# CANBedDualGd.net
KiCad netlist of a schematic drawn in EAGLE
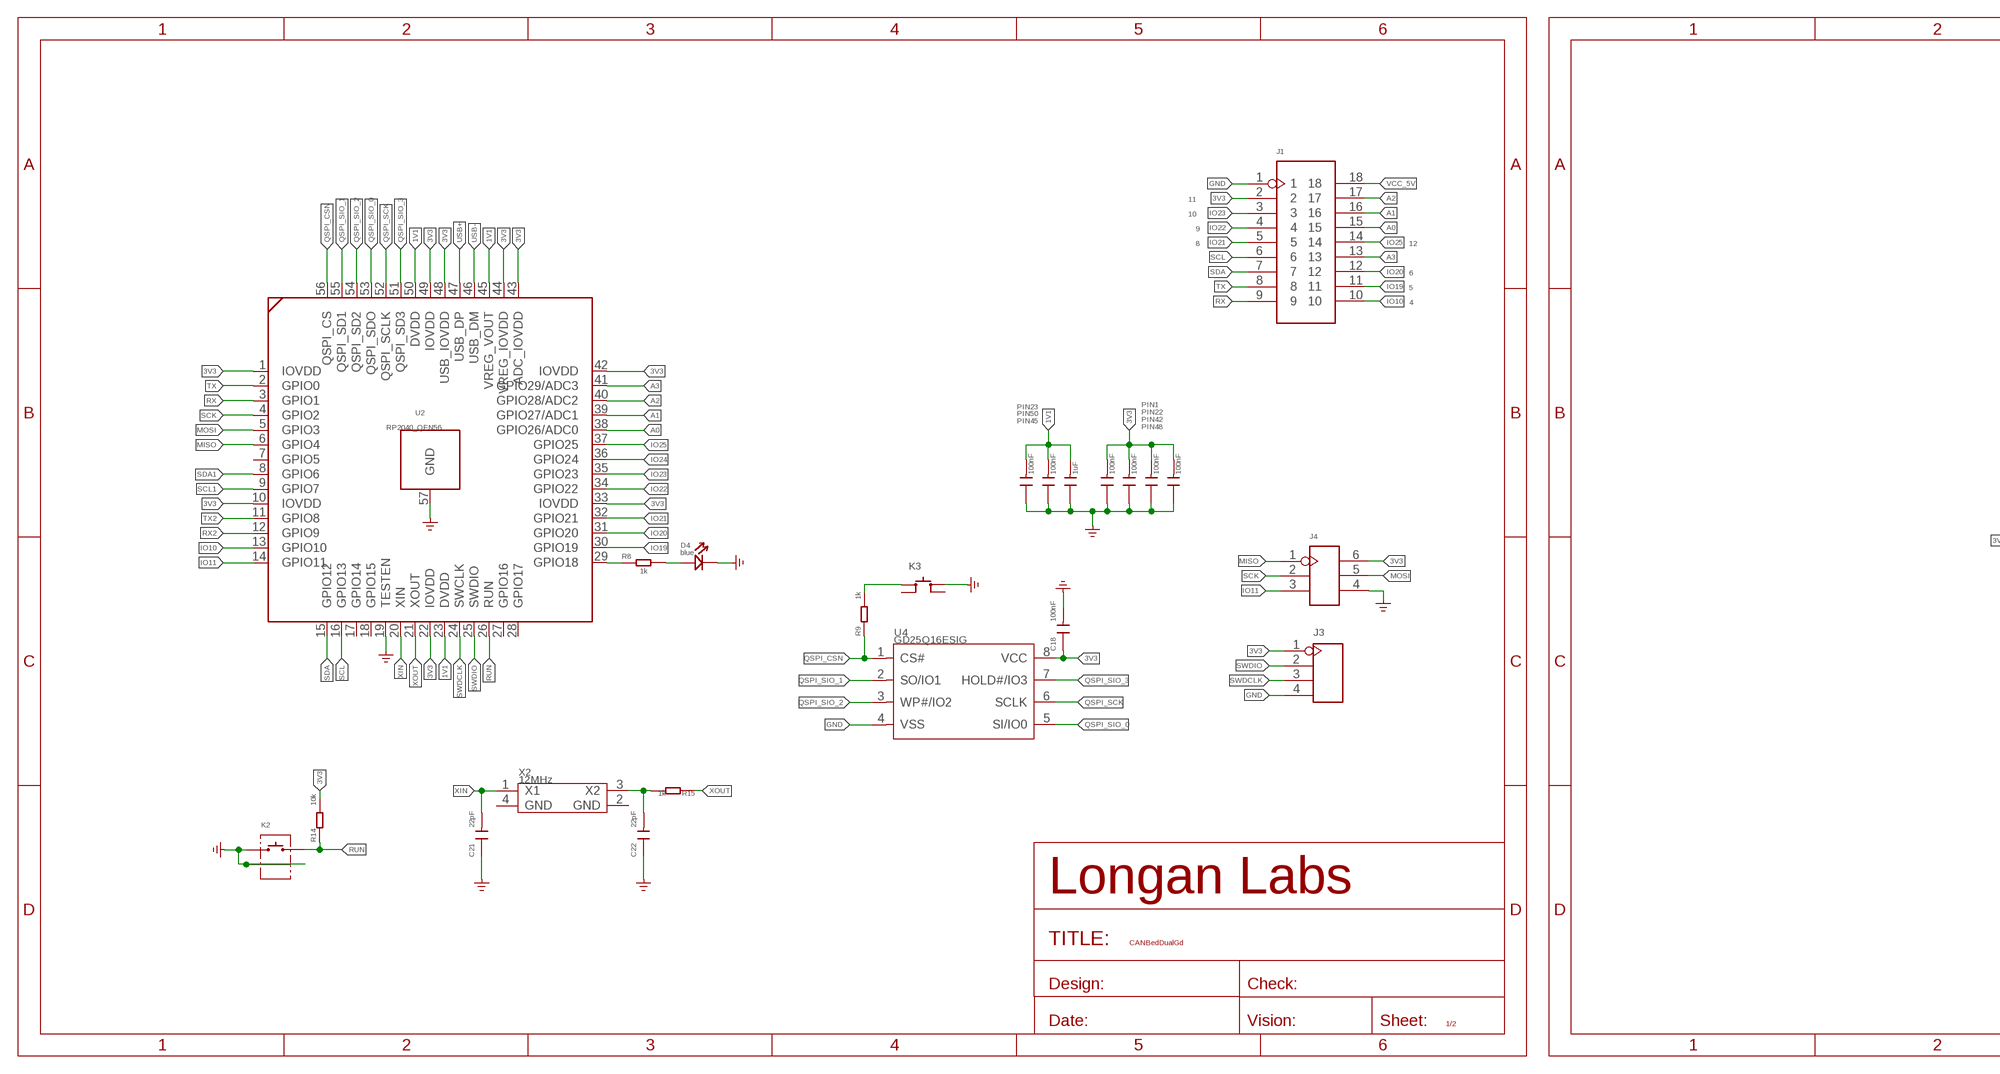
[diagram p0: schematic, sheet 1, part 1 of 2]
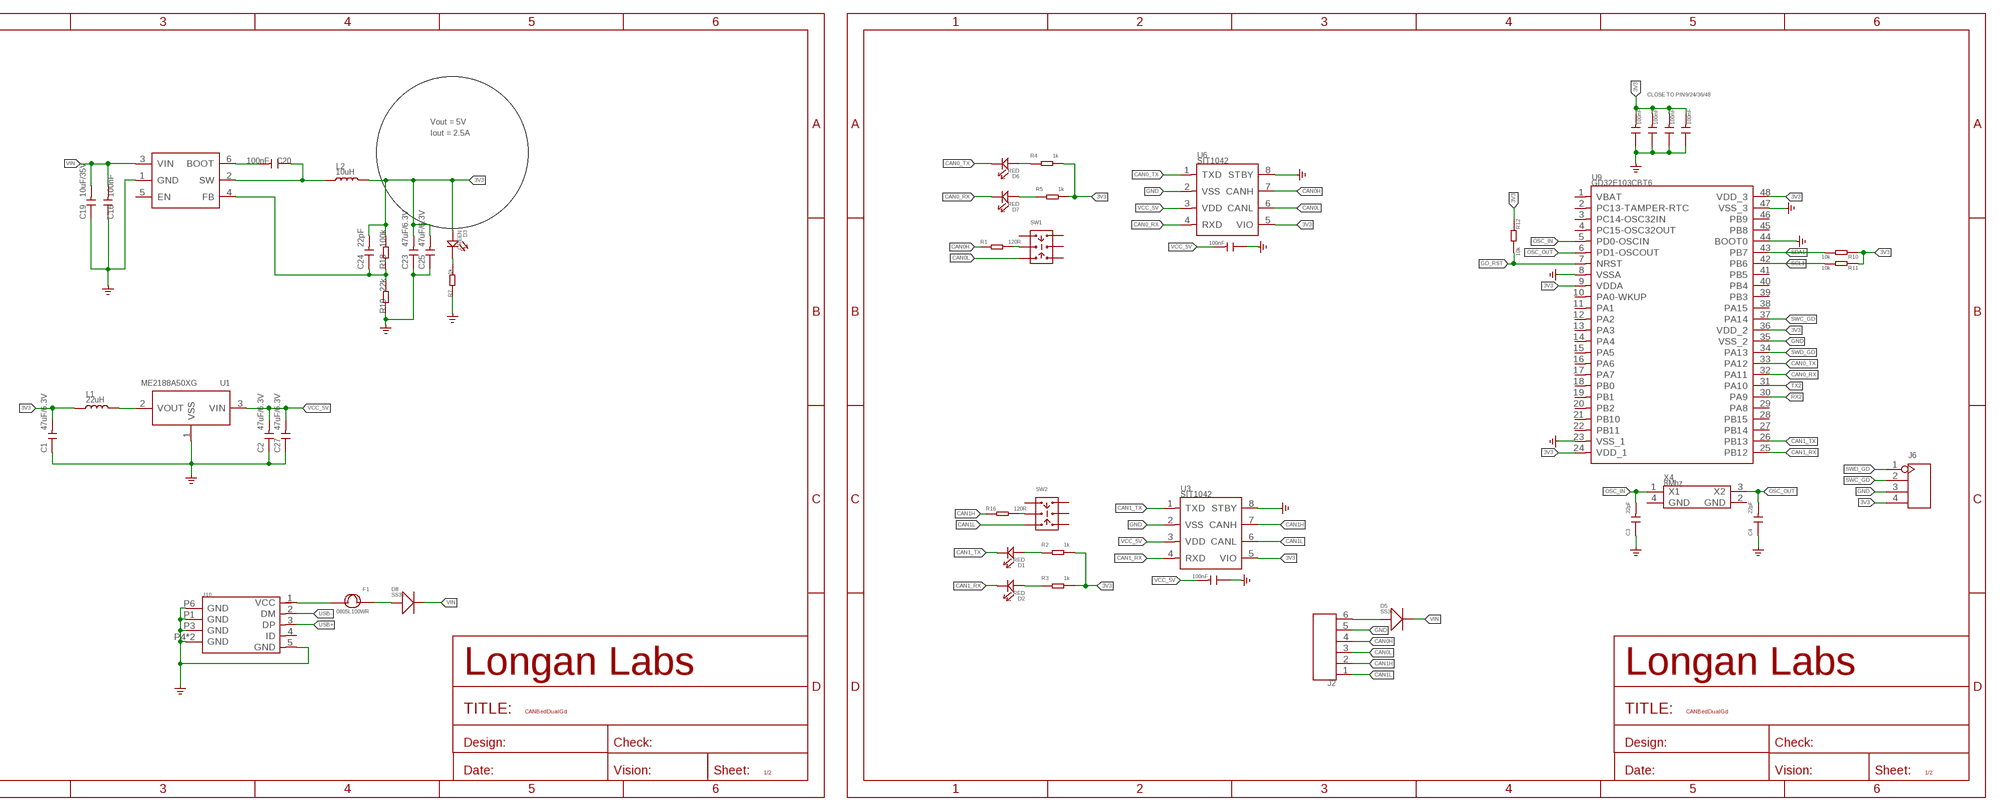
[diagram p1: schematic, sheet 1, part 2 of 2]

(export (version "E")
  (design (tool "Eeschema 10.0.6"))
  (components
    (comp (ref "C1")
      (value "47uF/6.3V")
      (footprint "eagle-import:C0805")
      (libsource (lib "eagle-import") (part "CAP-0805"))
    )
    (comp (ref "C2")
      (value "47uF/6.3V")
      (footprint "eagle-import:C0805")
      (libsource (lib "eagle-import") (part "CAP-0805"))
    )
    (comp (ref "C3")
      (value "22pF")
      (footprint "eagle-import:C0603")
      (libsource (lib "eagle-import") (part "CAP-0603"))
    )
    (comp (ref "C4")
      (value "22pF")
      (footprint "eagle-import:C0603")
      (libsource (lib "eagle-import") (part "CAP-0603"))
    )
    (comp (ref "C5")
      (value "100nF")
      (footprint "eagle-import:C0603")
      (libsource (lib "eagle-import") (part "CAP-0603"))
    )
    (comp (ref "C6")
      (value "100nF")
      (footprint "eagle-import:C0603")
      (libsource (lib "eagle-import") (part "CAP-0603"))
    )
    (comp (ref "C7")
      (value "100nF")
      (footprint "eagle-import:C0603")
      (libsource (lib "eagle-import") (part "CAP-0603"))
    )
    (comp (ref "C8")
      (value "100nF")
      (footprint "eagle-import:C0603")
      (libsource (lib "eagle-import") (part "CAP-0603"))
    )
    (comp (ref "C9")
      (value "100nF")
      (footprint "eagle-import:C0603")
      (libsource (lib "eagle-import") (part "CAP-0603"))
    )
    (comp (ref "C10")
      (value "100nF")
      (footprint "eagle-import:C0603")
      (libsource (lib "eagle-import") (part "CAP-0603"))
    )
    (comp (ref "C11")
      (value "1uF")
      (footprint "eagle-import:C0603")
      (libsource (lib "eagle-import") (part "CAP-0603"))
    )
    (comp (ref "C12")
      (value "100nF")
      (footprint "eagle-import:C0603")
      (libsource (lib "eagle-import") (part "CAP-0603"))
    )
    (comp (ref "C13")
      (value "100nF")
      (footprint "eagle-import:C0603")
      (libsource (lib "eagle-import") (part "CAP-0603"))
    )
    (comp (ref "C14")
      (value "100nF")
      (footprint "eagle-import:C0603")
      (libsource (lib "eagle-import") (part "CAP-0603"))
    )
    (comp (ref "C15")
      (value "100nF")
      (footprint "eagle-import:C0603")
      (libsource (lib "eagle-import") (part "CAP-0603"))
    )
    (comp (ref "C16")
      (value "100nF")
      (footprint "eagle-import:C0603")
      (libsource (lib "eagle-import") (part "CAP-0603"))
    )
    (comp (ref "C17")
      (value "100nF")
      (footprint "eagle-import:C0603")
      (libsource (lib "eagle-import") (part "CAP-0603"))
    )
    (comp (ref "C18")
      (value "100nF")
      (footprint "eagle-import:C0603")
      (libsource (lib "eagle-import") (part "CAP-0603"))
    )
    (comp (ref "C19")
      (value "10uF/35V")
      (footprint "eagle-import:C1206")
      (libsource (lib "eagle-import") (part "CAP-1206"))
    )
    (comp (ref "C20")
      (value "100nF")
      (footprint "eagle-import:C0603")
      (libsource (lib "eagle-import") (part "CAP-0603"))
    )
    (comp (ref "C21")
      (value "22pF")
      (footprint "eagle-import:C0603")
      (libsource (lib "eagle-import") (part "CAP-0603"))
    )
    (comp (ref "C22")
      (value "22pF")
      (footprint "eagle-import:C0603")
      (libsource (lib "eagle-import") (part "CAP-0603"))
    )
    (comp (ref "C23")
      (value "47uF/6.3V")
      (footprint "eagle-import:C0805")
      (libsource (lib "eagle-import") (part "CAP-0805"))
    )
    (comp (ref "C24")
      (value "22pF")
      (footprint "eagle-import:C0603")
      (libsource (lib "eagle-import") (part "CAP-0603"))
    )
    (comp (ref "C25")
      (value "47uF/6.3V")
      (footprint "eagle-import:C0805")
      (libsource (lib "eagle-import") (part "CAP-0805"))
    )
    (comp (ref "C26")
      (value "100nF")
      (footprint "eagle-import:C0603")
      (libsource (lib "eagle-import") (part "CAP-0603"))
    )
    (comp (ref "C27")
      (value "47uF/6.3V")
      (footprint "eagle-import:C0805")
      (libsource (lib "eagle-import") (part "CAP-0805"))
    )
    (comp (ref "D1")
      (value "RED")
      (footprint "eagle-import:LED-0603")
      (libsource (lib "eagle-import") (part "LED'0603'"))
    )
    (comp (ref "D2")
      (value "RED")
      (footprint "eagle-import:LED-0603")
      (libsource (lib "eagle-import") (part "LED'0603'"))
    )
    (comp (ref "D3")
      (value "GREEN")
      (footprint "eagle-import:LED-0603")
      (libsource (lib "eagle-import") (part "LED'0603'"))
    )
    (comp (ref "D4")
      (value "blue")
      (footprint "eagle-import:LED-0603")
      (libsource (lib "eagle-import") (part "LED'0603'"))
    )
    (comp (ref "D5")
      (value "SS32")
      (footprint "eagle-import:DO-214AC")
      (libsource (lib "eagle-import") (part "DIODE'SMA'"))
    )
    (comp (ref "D6")
      (value "RED")
      (footprint "eagle-import:LED-0603")
      (libsource (lib "eagle-import") (part "LED'0603'"))
    )
    (comp (ref "D7")
      (value "RED")
      (footprint "eagle-import:LED-0603")
      (libsource (lib "eagle-import") (part "LED'0603'"))
    )
    (comp (ref "D8")
      (value "SS32")
      (footprint "eagle-import:DO-214AC")
      (libsource (lib "eagle-import") (part "DIODE'SMA'"))
    )
    (comp (ref "F1")
      (value "0805L100WR")
      (footprint "eagle-import:F0805")
      (libsource (lib "eagle-import") (part "FUSE0805"))
    )
    (comp (ref "J1")
      (value "HEADER-2X9P-2.54")
      (footprint "eagle-import:H2X9-2.54")
      (libsource (lib "eagle-import") (part "HEADER-2X9P-2.54"))
    )
    (comp (ref "J2")
      (value "SCREW-TERMINAL-6P-3.5")
      (footprint "eagle-import:H6-3.5-21.7X7.0MM")
      (libsource (lib "eagle-import") (part "SCREW-TERMINAL-6P-3.5"))
    )
    (comp (ref "J3")
      (value "HEADER-4P-SMD")
      (footprint "eagle-import:H4-SMD-2.54")
      (libsource (lib "eagle-import") (part "HEADER-4P-SMD"))
    )
    (comp (ref "J4")
      (value "HEADER-2X3P-2.54")
      (footprint "eagle-import:H2X3-2.54")
      (libsource (lib "eagle-import") (part "HEADER-2X3P-2.54"))
    )
    (comp (ref "J6")
      (value "HEADER-4P-SMD")
      (footprint "eagle-import:H4-SMD-2.54")
      (libsource (lib "eagle-import") (part "HEADER-4P-SMD"))
    )
    (comp (ref "J10")
      (value "MICRO-USB5+4P-320010050")
      (footprint "eagle-import:MICRO-USB5+5P-SMD-0.65-7.2X5.06MM")
      (libsource (lib "eagle-import") (part "MICRO-USB5+4P-320010050"))
    )
    (comp (ref "K2")
      (value "BUTTON-2+2P")
      (footprint "eagle-import:SW2+2P-7.7X2.75X3.95MM")
      (libsource (lib "eagle-import") (part "BUTTON-2+2P"))
    )
    (comp (ref "K3")
      (value "BUTTON-4P-4.5X4.5X3.3MM")
      (footprint "eagle-import:SW4-4.5X4.5X3.3MM")
      (libsource (lib "eagle-import") (part "BUTTON-4P-4.5X4.5X3.3MM"))
    )
    (comp (ref "L1")
      (value "22uH")
      (footprint "eagle-import:L3030-TAIYO-YUDEN-NR3012")
      (libsource (lib "eagle-import") (part "INDUCTOR-3030"))
    )
    (comp (ref "L2")
      (value "10uH")
      (footprint "eagle-import:L0420")
      (libsource (lib "eagle-import") (part "INDUCTOR-SPD3D16-4R7M"))
    )
    (comp (ref "R1")
      (value "120R")
      (footprint "eagle-import:R0603")
      (libsource (lib "eagle-import") (part "RES-0603"))
    )
    (comp (ref "R2")
      (value "1k")
      (footprint "eagle-import:R0603")
      (libsource (lib "eagle-import") (part "RES-0603"))
    )
    (comp (ref "R3")
      (value "1k")
      (footprint "eagle-import:R0603")
      (libsource (lib "eagle-import") (part "RES-0603"))
    )
    (comp (ref "R4")
      (value "1k")
      (footprint "eagle-import:R0603")
      (libsource (lib "eagle-import") (part "RES-0603"))
    )
    (comp (ref "R5")
      (value "1k")
      (footprint "eagle-import:R0603")
      (libsource (lib "eagle-import") (part "RES-0603"))
    )
    (comp (ref "R7")
      (value "1k")
      (footprint "eagle-import:R0603")
      (libsource (lib "eagle-import") (part "RES-0603"))
    )
    (comp (ref "R8")
      (value "1k")
      (footprint "eagle-import:R0603")
      (libsource (lib "eagle-import") (part "RES-0603"))
    )
    (comp (ref "R9")
      (value "1k")
      (footprint "eagle-import:R0603")
      (libsource (lib "eagle-import") (part "RES-0603"))
    )
    (comp (ref "R10")
      (value "10k")
      (footprint "eagle-import:R0603")
      (libsource (lib "eagle-import") (part "RES-0603"))
    )
    (comp (ref "R11")
      (value "10k")
      (footprint "eagle-import:R0603")
      (libsource (lib "eagle-import") (part "RES-0603"))
    )
    (comp (ref "R12")
      (value "10k")
      (footprint "eagle-import:R0603")
      (libsource (lib "eagle-import") (part "RES-0603"))
    )
    (comp (ref "R14")
      (value "10k")
      (footprint "eagle-import:R0603")
      (libsource (lib "eagle-import") (part "RES-0603"))
    )
    (comp (ref "R15")
      (value "1k")
      (footprint "eagle-import:R0603")
      (libsource (lib "eagle-import") (part "RES-0603"))
    )
    (comp (ref "R16")
      (value "120R")
      (footprint "eagle-import:R0603")
      (libsource (lib "eagle-import") (part "RES-0603"))
    )
    (comp (ref "R18")
      (value "100k")
      (footprint "eagle-import:R0603")
      (libsource (lib "eagle-import") (part "RES-0603"))
    )
    (comp (ref "R19")
      (value "22k")
      (footprint "eagle-import:R0603")
      (libsource (lib "eagle-import") (part "RES-0603"))
    )
    (comp (ref "SW1")
      (value "SWITCH-2CH-6P-311010004")
      (footprint "eagle-import:SW6-2.54-9.0X3.5X3.2+2.0MM")
      (libsource (lib "eagle-import") (part "SWITCH-2CH-6P-311010004"))
    )
    (comp (ref "SW2")
      (value "SWITCH-2CH-6P-311010004")
      (footprint "eagle-import:SW6-2.54-9.0X3.5X3.2+2.0MM")
      (libsource (lib "eagle-import") (part "SWITCH-2CH-6P-311010004"))
    )
    (comp (ref "U1")
      (value "ME2188A50XG")
      (footprint "eagle-import:SOT-23")
      (libsource (lib "eagle-import") (part "PMIC-XC6206PMR"))
    )
    (comp (ref "U2")
      (value "RP2040_QFN56")
      (footprint "eagle-import:RP2040_QFN56")
      (libsource (lib "eagle-import") (part "RP2040_QFN56"))
    )
    (comp (ref "U3")
      (value "SIT1042")
      (footprint "eagle-import:SOIC8-1.27-5X4MM")
      (libsource (lib "eagle-import") (part "TRANSCEIVER-MCP2542"))
    )
    (comp (ref "U4")
      (value "GD25Q16ESIG")
      (footprint "eagle-import:SOP8-1.27-5.3X5.25X2MM")
      (libsource (lib "eagle-import") (part "FLASH-GD25Q16E"))
    )
    (comp (ref "U5")
      (value "PMIC-TPS54302")
      (footprint "eagle-import:SOT-23-6")
      (libsource (lib "eagle-import") (part "PMIC-TPS54302"))
    )
    (comp (ref "U6")
      (value "SIT1042")
      (footprint "eagle-import:SOIC8-1.27-5X4MM")
      (libsource (lib "eagle-import") (part "TRANSCEIVER-MCP2542"))
    )
    (comp (ref "U9")
      (value "GD32E103CBT6")
      (footprint "eagle-import:LQFP48")
      (libsource (lib "eagle-import") (part "MCU-GD32E103CBT6"))
    )
    (comp (ref "X2")
      (value "12MHz")
      (footprint "eagle-import:X4-SMD-3.2X2.5X0.7MM")
      (libsource (lib "eagle-import") (part "CRYSTAL-4P-3225"))
    )
    (comp (ref "X4")
      (value "8Mhz")
      (footprint "eagle-import:X4-SMD-3.2X2.5X0.7MM")
      (libsource (lib "eagle-import") (part "CRYSTAL-4P-3225"))
    )
  )
  (nets
    (net (code "1") (name "1V1") (class "Default")
      (node (ref "C10") (pin "2") (pinfunction "2_2") (pintype "passive"))
      (node (ref "C11") (pin "2") (pinfunction "2_2") (pintype "passive"))
      (node (ref "C9") (pin "2") (pinfunction "2_2") (pintype "passive"))
      (node (ref "U2") (pin "23") (pinfunction "DVDD_23") (pintype "bidirectional"))
      (node (ref "U2") (pin "45") (pinfunction "VREG_VOUT_45") (pintype "bidirectional"))
      (node (ref "U2") (pin "50") (pinfunction "DVDD_50") (pintype "bidirectional"))
    )
    (net (code "2") (name "3V3") (class "Default")
      (node (ref "C1") (pin "2") (pinfunction "2_2") (pintype "passive"))
      (node (ref "C12") (pin "2") (pinfunction "2_2") (pintype "passive"))
      (node (ref "C13") (pin "2") (pinfunction "2_2") (pintype "passive"))
      (node (ref "C14") (pin "2") (pinfunction "2_2") (pintype "passive"))
      (node (ref "C15") (pin "2") (pinfunction "2_2") (pintype "passive"))
      (node (ref "C18") (pin "1") (pinfunction "1_1") (pintype "passive"))
      (node (ref "C23") (pin "2") (pinfunction "2_2") (pintype "passive"))
      (node (ref "C24") (pin "2") (pinfunction "2_2") (pintype "passive"))
      (node (ref "C25") (pin "2") (pinfunction "2_2") (pintype "passive"))
      (node (ref "C5") (pin "2") (pinfunction "2_2") (pintype "passive"))
      (node (ref "C6") (pin "2") (pinfunction "2_2") (pintype "passive"))
      (node (ref "C7") (pin "2") (pinfunction "2_2") (pintype "passive"))
      (node (ref "C8") (pin "2") (pinfunction "2_2") (pintype "passive"))
      (node (ref "D3") (pin "+") (pinfunction "+_+") (pintype "passive"))
      (node (ref "J1") (pin "2") (pinfunction "2_2") (pintype "bidirectional"))
      (node (ref "J3") (pin "1") (pinfunction "P$1_1") (pintype "bidirectional"))
      (node (ref "J4") (pin "6") (pinfunction "6_6") (pintype "bidirectional"))
      (node (ref "J6") (pin "4") (pinfunction "P$4_4") (pintype "bidirectional"))
      (node (ref "L1") (pin "1") (pinfunction "1_1") (pintype "passive"))
      (node (ref "L2") (pin "2") (pinfunction "2_2") (pintype "passive"))
      (node (ref "R10") (pin "1") (pinfunction "1_1") (pintype "passive"))
      (node (ref "R11") (pin "1") (pinfunction "1_1") (pintype "passive"))
      (node (ref "R12") (pin "1") (pinfunction "1_1") (pintype "passive"))
      (node (ref "R14") (pin "2") (pinfunction "2_2") (pintype "passive"))
      (node (ref "R18") (pin "2") (pinfunction "2_2") (pintype "passive"))
      (node (ref "R2") (pin "2") (pinfunction "2_2") (pintype "passive"))
      (node (ref "R3") (pin "2") (pinfunction "2_2") (pintype "passive"))
      (node (ref "R4") (pin "2") (pinfunction "2_2") (pintype "passive"))
      (node (ref "R5") (pin "2") (pinfunction "2_2") (pintype "passive"))
      (node (ref "U2") (pin "1") (pinfunction "IOVDD_1") (pintype "bidirectional"))
      (node (ref "U2") (pin "10") (pinfunction "IOVDD_10") (pintype "bidirectional"))
      (node (ref "U2") (pin "22") (pinfunction "IOVDD_22") (pintype "bidirectional"))
      (node (ref "U2") (pin "33") (pinfunction "IOVDD_33") (pintype "bidirectional"))
      (node (ref "U2") (pin "42") (pinfunction "IOVDD_42") (pintype "bidirectional"))
      (node (ref "U2") (pin "43") (pinfunction "ADC_IOVDD_43") (pintype "bidirectional"))
      (node (ref "U2") (pin "44") (pinfunction "VREG_IOVDD_44") (pintype "bidirectional"))
      (node (ref "U2") (pin "48") (pinfunction "USB_IOVDD_48") (pintype "bidirectional"))
      (node (ref "U2") (pin "49") (pinfunction "IOVDD_49") (pintype "bidirectional"))
      (node (ref "U3") (pin "5") (pinfunction "VIO_5") (pintype "bidirectional"))
      (node (ref "U4") (pin "8") (pinfunction "VCC_8") (pintype "bidirectional"))
      (node (ref "U6") (pin "5") (pinfunction "VIO_5") (pintype "bidirectional"))
      (node (ref "U9") (pin "24") (pinfunction "VDD_1_24") (pintype "bidirectional"))
      (node (ref "U9") (pin "36") (pinfunction "VDD_2_36") (pintype "bidirectional"))
      (node (ref "U9") (pin "48") (pinfunction "VDD_3_48") (pintype "bidirectional"))
      (node (ref "U9") (pin "9") (pinfunction "VDDA_9") (pintype "bidirectional"))
    )
    (net (code "3") (name "A0") (class "Default")
      (node (ref "J1") (pin "15") (pinfunction "15_15") (pintype "bidirectional"))
      (node (ref "U2") (pin "38") (pinfunction "GPIO26/ADC0_38") (pintype "bidirectional"))
    )
    (net (code "4") (name "A1") (class "Default")
      (node (ref "J1") (pin "16") (pinfunction "16_16") (pintype "bidirectional"))
      (node (ref "U2") (pin "39") (pinfunction "GPIO27/ADC1_39") (pintype "bidirectional"))
    )
    (net (code "5") (name "A2") (class "Default")
      (node (ref "J1") (pin "17") (pinfunction "17_17") (pintype "bidirectional"))
      (node (ref "U2") (pin "40") (pinfunction "GPIO28/ADC2_40") (pintype "bidirectional"))
    )
    (net (code "6") (name "A3") (class "Default")
      (node (ref "J1") (pin "13") (pinfunction "13_13") (pintype "bidirectional"))
      (node (ref "U2") (pin "41") (pinfunction "GPIO29/ADC3_41") (pintype "bidirectional"))
    )
    (net (code "7") (name "CAN0H") (class "Default")
      (node (ref "J2") (pin "4") (pinfunction "4_4") (pintype "bidirectional"))
      (node (ref "R1") (pin "1") (pinfunction "1_1") (pintype "passive"))
      (node (ref "U6") (pin "7") (pinfunction "CANH_7") (pintype "bidirectional"))
    )
    (net (code "8") (name "CAN0L") (class "Default")
      (node (ref "J2") (pin "3") (pinfunction "3_3") (pintype "bidirectional"))
      (node (ref "SW1") (pin "CH1B") (pinfunction "CH1B_CH1B") (pintype "bidirectional"))
      (node (ref "U6") (pin "6") (pinfunction "CANL_6") (pintype "bidirectional"))
    )
    (net (code "9") (name "CAN0_RX") (class "Default")
      (node (ref "D7") (pin "-") (pinfunction "-_-") (pintype "passive"))
      (node (ref "U6") (pin "4") (pinfunction "RXD_4") (pintype "bidirectional"))
      (node (ref "U9") (pin "32") (pinfunction "PA11_32") (pintype "bidirectional"))
    )
    (net (code "10") (name "CAN0_TX") (class "Default")
      (node (ref "D6") (pin "-") (pinfunction "-_-") (pintype "passive"))
      (node (ref "U6") (pin "1") (pinfunction "TXD_1") (pintype "bidirectional"))
      (node (ref "U9") (pin "33") (pinfunction "PA12_33") (pintype "bidirectional"))
    )
    (net (code "11") (name "CAN1H") (class "Default")
      (node (ref "J2") (pin "2") (pinfunction "2_2") (pintype "bidirectional"))
      (node (ref "R16") (pin "1") (pinfunction "1_1") (pintype "passive"))
      (node (ref "U3") (pin "7") (pinfunction "CANH_7") (pintype "bidirectional"))
    )
    (net (code "12") (name "CAN1L") (class "Default")
      (node (ref "J2") (pin "1") (pinfunction "1_1") (pintype "bidirectional"))
      (node (ref "SW2") (pin "CH1B") (pinfunction "CH1B_CH1B") (pintype "bidirectional"))
      (node (ref "U3") (pin "6") (pinfunction "CANL_6") (pintype "bidirectional"))
    )
    (net (code "13") (name "CAN1_RX") (class "Default")
      (node (ref "D2") (pin "-") (pinfunction "-_-") (pintype "passive"))
      (node (ref "U3") (pin "4") (pinfunction "RXD_4") (pintype "bidirectional"))
      (node (ref "U9") (pin "25") (pinfunction "PB12_25") (pintype "bidirectional"))
    )
    (net (code "14") (name "CAN1_TX") (class "Default")
      (node (ref "D1") (pin "-") (pinfunction "-_-") (pintype "passive"))
      (node (ref "U3") (pin "1") (pinfunction "TXD_1") (pintype "bidirectional"))
      (node (ref "U9") (pin "26") (pinfunction "PB13_26") (pintype "bidirectional"))
    )
    (net (code "15") (name "GD_RST") (class "Default")
      (node (ref "R12") (pin "2") (pinfunction "2_2") (pintype "passive"))
      (node (ref "U9") (pin "7") (pinfunction "NRST_7") (pintype "bidirectional"))
    )
    (net (code "16") (name "GND") (class "Default")
      (node (ref "C1") (pin "1") (pinfunction "1_1") (pintype "passive"))
      (node (ref "C10") (pin "1") (pinfunction "1_1") (pintype "passive"))
      (node (ref "C11") (pin "1") (pinfunction "1_1") (pintype "passive"))
      (node (ref "C12") (pin "1") (pinfunction "1_1") (pintype "passive"))
      (node (ref "C13") (pin "1") (pinfunction "1_1") (pintype "passive"))
      (node (ref "C14") (pin "1") (pinfunction "1_1") (pintype "passive"))
      (node (ref "C15") (pin "1") (pinfunction "1_1") (pintype "passive"))
      (node (ref "C16") (pin "1") (pinfunction "1_1") (pintype "passive"))
      (node (ref "C17") (pin "1") (pinfunction "1_1") (pintype "passive"))
      (node (ref "C18") (pin "2") (pinfunction "2_2") (pintype "passive"))
      (node (ref "C19") (pin "1") (pinfunction "1_1") (pintype "passive"))
      (node (ref "C2") (pin "1") (pinfunction "1_1") (pintype "passive"))
      (node (ref "C21") (pin "1") (pinfunction "1_1") (pintype "passive"))
      (node (ref "C22") (pin "1") (pinfunction "1_1") (pintype "passive"))
      (node (ref "C23") (pin "1") (pinfunction "1_1") (pintype "passive"))
      (node (ref "C25") (pin "1") (pinfunction "1_1") (pintype "passive"))
      (node (ref "C26") (pin "1") (pinfunction "1_1") (pintype "passive"))
      (node (ref "C27") (pin "1") (pinfunction "1_1") (pintype "passive"))
      (node (ref "C3") (pin "1") (pinfunction "1_1") (pintype "passive"))
      (node (ref "C4") (pin "1") (pinfunction "1_1") (pintype "passive"))
      (node (ref "C5") (pin "1") (pinfunction "1_1") (pintype "passive"))
      (node (ref "C6") (pin "1") (pinfunction "1_1") (pintype "passive"))
      (node (ref "C7") (pin "1") (pinfunction "1_1") (pintype "passive"))
      (node (ref "C8") (pin "1") (pinfunction "1_1") (pintype "passive"))
      (node (ref "C9") (pin "1") (pinfunction "1_1") (pintype "passive"))
      (node (ref "D4") (pin "-") (pinfunction "-_-") (pintype "passive"))
      (node (ref "J1") (pin "1") (pinfunction "1_1") (pintype "bidirectional"))
      (node (ref "J10") (pin "5") (pinfunction "GND_5") (pintype "bidirectional"))
      (node (ref "J10") (pin "P1") (pinfunction "GND_P1") (pintype "bidirectional"))
      (node (ref "J10") (pin "P3") (pinfunction "GND_P3") (pintype "bidirectional"))
      (node (ref "J10") (pin "P4") (pinfunction "GND_P4") (pintype "bidirectional"))
      (node (ref "J10") (pin "P5") (pinfunction "GND_P5") (pintype "bidirectional"))
      (node (ref "J10") (pin "P6") (pinfunction "GND_P6") (pintype "bidirectional"))
      (node (ref "J2") (pin "5") (pinfunction "5_5") (pintype "bidirectional"))
      (node (ref "J3") (pin "4") (pinfunction "P$4_4") (pintype "bidirectional"))
      (node (ref "J4") (pin "4") (pinfunction "4_4") (pintype "bidirectional"))
      (node (ref "J6") (pin "3") (pinfunction "P$3_3") (pintype "bidirectional"))
      (node (ref "K2") (pin "1") (pinfunction "1_1") (pintype "bidirectional"))
      (node (ref "K2") (pin "S1") (pinfunction "S1_S1") (pintype "bidirectional"))
      (node (ref "K2") (pin "S2") (pinfunction "S2_S2") (pintype "bidirectional"))
      (node (ref "K3") (pin "3") (pinfunction "B0_3") (pintype "bidirectional"))
      (node (ref "R19") (pin "1") (pinfunction "1_1") (pintype "passive"))
      (node (ref "R7") (pin "1") (pinfunction "1_1") (pintype "passive"))
      (node (ref "U1") (pin "1") (pinfunction "VSS_1") (pintype "bidirectional"))
      (node (ref "U2") (pin "19") (pinfunction "TESTEN_19") (pintype "bidirectional"))
      (node (ref "U2") (pin "57") (pinfunction "GND_57") (pintype "bidirectional"))
      (node (ref "U3") (pin "2") (pinfunction "VSS_2") (pintype "bidirectional"))
      (node (ref "U3") (pin "8") (pinfunction "STBY_8") (pintype "bidirectional"))
      (node (ref "U4") (pin "4") (pinfunction "VSS_4") (pintype "bidirectional"))
      (node (ref "U5") (pin "1") (pinfunction "GND_1") (pintype "bidirectional"))
      (node (ref "U6") (pin "2") (pinfunction "VSS_2") (pintype "bidirectional"))
      (node (ref "U6") (pin "8") (pinfunction "STBY_8") (pintype "bidirectional"))
      (node (ref "U9") (pin "23") (pinfunction "VSS_1_23") (pintype "bidirectional"))
      (node (ref "U9") (pin "35") (pinfunction "VSS_2_35") (pintype "bidirectional"))
      (node (ref "U9") (pin "44") (pinfunction "BOOT0_44") (pintype "bidirectional"))
      (node (ref "U9") (pin "47") (pinfunction "VSS_3_47") (pintype "bidirectional"))
      (node (ref "U9") (pin "8") (pinfunction "VSSA_8") (pintype "bidirectional"))
    )
    (net (code "17") (name "IO10") (class "Default")
      (node (ref "J1") (pin "10") (pinfunction "10_10") (pintype "bidirectional"))
      (node (ref "U2") (pin "13") (pinfunction "GPIO10_13") (pintype "bidirectional"))
    )
    (net (code "18") (name "IO11") (class "Default")
      (node (ref "J4") (pin "3") (pinfunction "3_3") (pintype "bidirectional"))
      (node (ref "U2") (pin "14") (pinfunction "GPIO11_14") (pintype "bidirectional"))
    )
    (net (code "19") (name "IO19") (class "Default")
      (node (ref "J1") (pin "11") (pinfunction "11_11") (pintype "bidirectional"))
      (node (ref "U2") (pin "30") (pinfunction "GPIO19_30") (pintype "bidirectional"))
    )
    (net (code "20") (name "IO20") (class "Default")
      (node (ref "J1") (pin "12") (pinfunction "12_12") (pintype "bidirectional"))
      (node (ref "U2") (pin "31") (pinfunction "GPIO20_31") (pintype "bidirectional"))
    )
    (net (code "21") (name "IO21") (class "Default")
      (node (ref "J1") (pin "5") (pinfunction "5_5") (pintype "bidirectional"))
      (node (ref "U2") (pin "32") (pinfunction "GPIO21_32") (pintype "bidirectional"))
    )
    (net (code "22") (name "IO22") (class "Default")
      (node (ref "J1") (pin "4") (pinfunction "4_4") (pintype "bidirectional"))
      (node (ref "U2") (pin "34") (pinfunction "GPIO22_34") (pintype "bidirectional"))
    )
    (net (code "23") (name "IO23") (class "Default")
      (node (ref "J1") (pin "3") (pinfunction "3_3") (pintype "bidirectional"))
      (node (ref "U2") (pin "35") (pinfunction "GPIO23_35") (pintype "bidirectional"))
    )
    (net (code "24") (name "IO24") (class "Default")
      (node (ref "U2") (pin "36") (pinfunction "GPIO24_36") (pintype "bidirectional"))
    )
    (net (code "25") (name "IO25") (class "Default")
      (node (ref "J1") (pin "14") (pinfunction "14_14") (pintype "bidirectional"))
      (node (ref "U2") (pin "37") (pinfunction "GPIO25_37") (pintype "bidirectional"))
    )
    (net (code "26") (name "MISO") (class "Default")
      (node (ref "J4") (pin "1") (pinfunction "1_1") (pintype "bidirectional"))
      (node (ref "U2") (pin "6") (pinfunction "GPIO4_6") (pintype "bidirectional"))
    )
    (net (code "27") (name "MOSI") (class "Default")
      (node (ref "J4") (pin "5") (pinfunction "5_5") (pintype "bidirectional"))
      (node (ref "U2") (pin "5") (pinfunction "GPIO3_5") (pintype "bidirectional"))
    )
    (net (code "28") (name "Net-(D1-Pad+)") (class "Default")
      (node (ref "D1") (pin "+") (pinfunction "+_+") (pintype "passive"))
      (node (ref "R2") (pin "1") (pinfunction "1_1") (pintype "passive"))
    )
    (net (code "29") (name "Net-(D2-Pad+)") (class "Default")
      (node (ref "D2") (pin "+") (pinfunction "+_+") (pintype "passive"))
      (node (ref "R3") (pin "1") (pinfunction "1_1") (pintype "passive"))
    )
    (net (code "30") (name "Net-(D3-Pad-)") (class "Default")
      (node (ref "D3") (pin "-") (pinfunction "-_-") (pintype "passive"))
      (node (ref "R7") (pin "2") (pinfunction "2_2") (pintype "passive"))
    )
    (net (code "31") (name "Net-(D4-Pad+)") (class "Default")
      (node (ref "D4") (pin "+") (pinfunction "+_+") (pintype "passive"))
      (node (ref "R8") (pin "2") (pinfunction "2_2") (pintype "passive"))
    )
    (net (code "32") (name "Net-(D5-+)") (class "Default")
      (node (ref "D5") (pin "1") (pinfunction "+_1") (pintype "passive"))
      (node (ref "J2") (pin "6") (pinfunction "6_6") (pintype "bidirectional"))
    )
    (net (code "33") (name "Net-(D6-Pad+)") (class "Default")
      (node (ref "D6") (pin "+") (pinfunction "+_+") (pintype "passive"))
      (node (ref "R4") (pin "1") (pinfunction "1_1") (pintype "passive"))
    )
    (net (code "34") (name "Net-(D7-Pad+)") (class "Default")
      (node (ref "D7") (pin "+") (pinfunction "+_+") (pintype "passive"))
      (node (ref "R5") (pin "1") (pinfunction "1_1") (pintype "passive"))
    )
    (net (code "35") (name "Net-(D8-+)") (class "Default")
      (node (ref "D8") (pin "1") (pinfunction "+_1") (pintype "passive"))
      (node (ref "F1") (pin "1") (pinfunction "1_1") (pintype "bidirectional"))
    )
    (net (code "36") (name "Net-(J10-VCC)") (class "Default")
      (node (ref "F1") (pin "2") (pinfunction "2_2") (pintype "bidirectional"))
      (node (ref "J10") (pin "1") (pinfunction "VCC_1") (pintype "bidirectional"))
    )
    (net (code "37") (name "Net-(K3-A0)") (class "Default")
      (node (ref "K3") (pin "1") (pinfunction "A0_1") (pintype "bidirectional"))
      (node (ref "R9") (pin "2") (pinfunction "2_2") (pintype "passive"))
    )
    (net (code "38") (name "Net-(R1-Pad2)") (class "Default")
      (node (ref "R1") (pin "2") (pinfunction "2_2") (pintype "passive"))
      (node (ref "SW1") (pin "COM1") (pinfunction "COM1_COM1") (pintype "bidirectional"))
    )
    (net (code "39") (name "Net-(R16-Pad2)") (class "Default")
      (node (ref "R16") (pin "2") (pinfunction "2_2") (pintype "passive"))
      (node (ref "SW2") (pin "COM1") (pinfunction "COM1_COM1") (pintype "bidirectional"))
    )
    (net (code "40") (name "Net-(U1-VOUT)") (class "Default")
      (node (ref "L1") (pin "2") (pinfunction "2_2") (pintype "passive"))
      (node (ref "U1") (pin "2") (pinfunction "VOUT_2") (pintype "bidirectional"))
    )
    (net (code "41") (name "Net-(U2-GPIO18)") (class "Default")
      (node (ref "R8") (pin "1") (pinfunction "1_1") (pintype "passive"))
      (node (ref "U2") (pin "29") (pinfunction "GPIO18_29") (pintype "bidirectional"))
    )
    (net (code "42") (name "Net-(U5-BOOT)") (class "Default")
      (node (ref "C20") (pin "2") (pinfunction "2_2") (pintype "passive"))
      (node (ref "U5") (pin "6") (pinfunction "BOOT_6") (pintype "bidirectional"))
    )
    (net (code "43") (name "Net-(U5-FB)") (class "Default")
      (node (ref "C24") (pin "1") (pinfunction "1_1") (pintype "passive"))
      (node (ref "R18") (pin "1") (pinfunction "1_1") (pintype "passive"))
      (node (ref "R19") (pin "2") (pinfunction "2_2") (pintype "passive"))
      (node (ref "U5") (pin "4") (pinfunction "FB_4") (pintype "bidirectional"))
    )
    (net (code "44") (name "Net-(U5-SW)") (class "Default")
      (node (ref "C20") (pin "1") (pinfunction "1_1") (pintype "passive"))
      (node (ref "L2") (pin "1") (pinfunction "1_1") (pintype "passive"))
      (node (ref "U5") (pin "2") (pinfunction "SW_2") (pintype "bidirectional"))
    )
    (net (code "45") (name "Net-(X2-X2)") (class "Default")
      (node (ref "C22") (pin "2") (pinfunction "2_2") (pintype "passive"))
      (node (ref "R15") (pin "2") (pinfunction "2_2") (pintype "passive"))
      (node (ref "X2") (pin "3") (pinfunction "X2_3") (pintype "bidirectional"))
    )
    (net (code "46") (name "OSC_IN") (class "Default")
      (node (ref "C3") (pin "2") (pinfunction "2_2") (pintype "passive"))
      (node (ref "U9") (pin "5") (pinfunction "PD0-OSCIN_5") (pintype "bidirectional"))
      (node (ref "X4") (pin "1") (pinfunction "X1_1") (pintype "bidirectional"))
    )
    (net (code "47") (name "OSC_OUT") (class "Default")
      (node (ref "C4") (pin "2") (pinfunction "2_2") (pintype "passive"))
      (node (ref "U9") (pin "6") (pinfunction "PD1-OSCOUT_6") (pintype "bidirectional"))
      (node (ref "X4") (pin "3") (pinfunction "X2_3") (pintype "bidirectional"))
    )
    (net (code "48") (name "QSPI_CSN") (class "Default")
      (node (ref "R9") (pin "1") (pinfunction "1_1") (pintype "passive"))
      (node (ref "U2") (pin "56") (pinfunction "QSPI_CS_56") (pintype "bidirectional"))
      (node (ref "U4") (pin "1") (pinfunction "CS#_1") (pintype "bidirectional"))
    )
    (net (code "49") (name "QSPI_SCK") (class "Default")
      (node (ref "U2") (pin "52") (pinfunction "QSPI_SCLK_52") (pintype "bidirectional"))
      (node (ref "U4") (pin "6") (pinfunction "SCLK_6") (pintype "bidirectional"))
    )
    (net (code "50") (name "QSPI_SIO_0") (class "Default")
      (node (ref "U2") (pin "53") (pinfunction "QSPI_SDO_53") (pintype "bidirectional"))
      (node (ref "U4") (pin "5") (pinfunction "SI/IO0_5") (pintype "bidirectional"))
    )
    (net (code "51") (name "QSPI_SIO_1") (class "Default")
      (node (ref "U2") (pin "55") (pinfunction "QSPI_SD1_55") (pintype "bidirectional"))
      (node (ref "U4") (pin "2") (pinfunction "SO/IO1_2") (pintype "bidirectional"))
    )
    (net (code "52") (name "QSPI_SIO_2") (class "Default")
      (node (ref "U2") (pin "54") (pinfunction "QSPI_SD2_54") (pintype "bidirectional"))
      (node (ref "U4") (pin "3") (pinfunction "WP#/IO2_3") (pintype "bidirectional"))
    )
    (net (code "53") (name "QSPI_SIO_3") (class "Default")
      (node (ref "U2") (pin "51") (pinfunction "QSPI_SD3_51") (pintype "bidirectional"))
      (node (ref "U4") (pin "7") (pinfunction "HOLD#/IO3_7") (pintype "bidirectional"))
    )
    (net (code "54") (name "RUN") (class "Default")
      (node (ref "K2") (pin "2") (pinfunction "2_2") (pintype "bidirectional"))
      (node (ref "R14") (pin "1") (pinfunction "1_1") (pintype "passive"))
      (node (ref "U2") (pin "26") (pinfunction "RUN_26") (pintype "bidirectional"))
    )
    (net (code "55") (name "RX") (class "Default")
      (node (ref "J1") (pin "9") (pinfunction "9_9") (pintype "bidirectional"))
      (node (ref "U2") (pin "3") (pinfunction "GPIO1_3") (pintype "bidirectional"))
    )
    (net (code "56") (name "RX2") (class "Default")
      (node (ref "U2") (pin "12") (pinfunction "GPIO9_12") (pintype "bidirectional"))
      (node (ref "U9") (pin "30") (pinfunction "PA9_30") (pintype "bidirectional"))
    )
    (net (code "57") (name "SCK") (class "Default")
      (node (ref "J4") (pin "2") (pinfunction "2_2") (pintype "bidirectional"))
      (node (ref "U2") (pin "4") (pinfunction "GPIO2_4") (pintype "bidirectional"))
    )
    (net (code "58") (name "SCL") (class "Default")
      (node (ref "J1") (pin "6") (pinfunction "6_6") (pintype "bidirectional"))
      (node (ref "U2") (pin "16") (pinfunction "GPIO13_16") (pintype "bidirectional"))
    )
    (net (code "59") (name "SCL1") (class "Default")
      (node (ref "R11") (pin "2") (pinfunction "2_2") (pintype "passive"))
      (node (ref "U2") (pin "9") (pinfunction "GPIO7_9") (pintype "bidirectional"))
      (node (ref "U9") (pin "42") (pinfunction "PB6_42") (pintype "bidirectional"))
    )
    (net (code "60") (name "SDA") (class "Default")
      (node (ref "J1") (pin "7") (pinfunction "7_7") (pintype "bidirectional"))
      (node (ref "U2") (pin "15") (pinfunction "GPIO12_15") (pintype "bidirectional"))
    )
    (net (code "61") (name "SDA1") (class "Default")
      (node (ref "R10") (pin "2") (pinfunction "2_2") (pintype "passive"))
      (node (ref "U2") (pin "8") (pinfunction "GPIO6_8") (pintype "bidirectional"))
      (node (ref "U9") (pin "43") (pinfunction "PB7_43") (pintype "bidirectional"))
    )
    (net (code "62") (name "SWC_GD") (class "Default")
      (node (ref "J6") (pin "2") (pinfunction "P$2_2") (pintype "bidirectional"))
      (node (ref "U9") (pin "37") (pinfunction "PA14_37") (pintype "bidirectional"))
    )
    (net (code "63") (name "SWDCLK") (class "Default")
      (node (ref "J3") (pin "3") (pinfunction "P$3_3") (pintype "bidirectional"))
      (node (ref "U2") (pin "24") (pinfunction "SWCLK_24") (pintype "bidirectional"))
    )
    (net (code "64") (name "SWDIO") (class "Default")
      (node (ref "J3") (pin "2") (pinfunction "P$2_2") (pintype "bidirectional"))
      (node (ref "U2") (pin "25") (pinfunction "SWDIO_25") (pintype "bidirectional"))
    )
    (net (code "65") (name "SWD_GD") (class "Default")
      (node (ref "J6") (pin "1") (pinfunction "P$1_1") (pintype "bidirectional"))
      (node (ref "U9") (pin "34") (pinfunction "PA13_34") (pintype "bidirectional"))
    )
    (net (code "66") (name "TX") (class "Default")
      (node (ref "J1") (pin "8") (pinfunction "8_8") (pintype "bidirectional"))
      (node (ref "U2") (pin "2") (pinfunction "GPIO0_2") (pintype "bidirectional"))
    )
    (net (code "67") (name "TX2") (class "Default")
      (node (ref "U2") (pin "11") (pinfunction "GPIO8_11") (pintype "bidirectional"))
      (node (ref "U9") (pin "31") (pinfunction "PA10_31") (pintype "bidirectional"))
    )
    (net (code "68") (name "USB+") (class "Default")
      (node (ref "J10") (pin "3") (pinfunction "DP_3") (pintype "bidirectional"))
      (node (ref "U2") (pin "47") (pinfunction "USB_DP_47") (pintype "bidirectional"))
    )
    (net (code "69") (name "USB-") (class "Default")
      (node (ref "J10") (pin "2") (pinfunction "DM_2") (pintype "bidirectional"))
      (node (ref "U2") (pin "46") (pinfunction "USB_DM_46") (pintype "bidirectional"))
    )
    (net (code "70") (name "VCC_5V") (class "Default")
      (node (ref "C17") (pin "2") (pinfunction "2_2") (pintype "passive"))
      (node (ref "C2") (pin "2") (pinfunction "2_2") (pintype "passive"))
      (node (ref "C26") (pin "2") (pinfunction "2_2") (pintype "passive"))
      (node (ref "C27") (pin "2") (pinfunction "2_2") (pintype "passive"))
      (node (ref "J1") (pin "18") (pinfunction "18_18") (pintype "bidirectional"))
      (node (ref "U1") (pin "3") (pinfunction "VIN_3") (pintype "bidirectional"))
      (node (ref "U3") (pin "3") (pinfunction "VDD_3") (pintype "bidirectional"))
      (node (ref "U6") (pin "3") (pinfunction "VDD_3") (pintype "bidirectional"))
    )
    (net (code "71") (name "VIN") (class "Default")
      (node (ref "C16") (pin "2") (pinfunction "2_2") (pintype "passive"))
      (node (ref "C19") (pin "2") (pinfunction "2_2") (pintype "passive"))
      (node (ref "D5") (pin "2") (pinfunction "-_2") (pintype "passive"))
      (node (ref "D8") (pin "2") (pinfunction "-_2") (pintype "passive"))
      (node (ref "U5") (pin "3") (pinfunction "VIN_3") (pintype "bidirectional"))
    )
    (net (code "72") (name "XIN") (class "Default")
      (node (ref "C21") (pin "2") (pinfunction "2_2") (pintype "passive"))
      (node (ref "U2") (pin "20") (pinfunction "XIN_20") (pintype "bidirectional"))
      (node (ref "X2") (pin "1") (pinfunction "X1_1") (pintype "bidirectional"))
    )
    (net (code "73") (name "XOUT") (class "Default")
      (node (ref "R15") (pin "1") (pinfunction "1_1") (pintype "passive"))
      (node (ref "U2") (pin "21") (pinfunction "XOUT_21") (pintype "bidirectional"))
    )
    (net (code "74") (name "unconnected-(J10-ID-Pad4)") (class "Default")
      (node (ref "J10") (pin "4") (pinfunction "ID_4") (pintype "bidirectional"))
    )
    (net (code "75") (name "unconnected-(K3-A1-Pad2)") (class "Default")
      (node (ref "K3") (pin "2") (pinfunction "A1_2") (pintype "bidirectional"))
    )
    (net (code "76") (name "unconnected-(K3-B1-Pad4)") (class "Default")
      (node (ref "K3") (pin "4") (pinfunction "B1_4") (pintype "bidirectional"))
    )
    (net (code "77") (name "unconnected-(SW1-PadCH1A)") (class "Default")
      (node (ref "SW1") (pin "CH1A") (pinfunction "CH1A_CH1A") (pintype "bidirectional"))
    )
    (net (code "78") (name "unconnected-(SW1-PadCH2A)") (class "Default")
      (node (ref "SW1") (pin "CH2A") (pinfunction "CH2A_CH2A") (pintype "bidirectional"))
    )
    (net (code "79") (name "unconnected-(SW1-PadCH2B)") (class "Default")
      (node (ref "SW1") (pin "CH2B") (pinfunction "CH2B_CH2B") (pintype "bidirectional"))
    )
    (net (code "80") (name "unconnected-(SW1-PadCOM2)") (class "Default")
      (node (ref "SW1") (pin "COM2") (pinfunction "COM2_COM2") (pintype "bidirectional"))
    )
    (net (code "81") (name "unconnected-(SW2-PadCH1A)") (class "Default")
      (node (ref "SW2") (pin "CH1A") (pinfunction "CH1A_CH1A") (pintype "bidirectional"))
    )
    (net (code "82") (name "unconnected-(SW2-PadCH2A)") (class "Default")
      (node (ref "SW2") (pin "CH2A") (pinfunction "CH2A_CH2A") (pintype "bidirectional"))
    )
    (net (code "83") (name "unconnected-(SW2-PadCH2B)") (class "Default")
      (node (ref "SW2") (pin "CH2B") (pinfunction "CH2B_CH2B") (pintype "bidirectional"))
    )
    (net (code "84") (name "unconnected-(SW2-PadCOM2)") (class "Default")
      (node (ref "SW2") (pin "COM2") (pinfunction "COM2_COM2") (pintype "bidirectional"))
    )
    (net (code "85") (name "unconnected-(U2-GPIO5-Pad7)") (class "Default")
      (node (ref "U2") (pin "7") (pinfunction "GPIO5_7") (pintype "bidirectional"))
    )
    (net (code "86") (name "unconnected-(U2-GPIO14-Pad17)") (class "Default")
      (node (ref "U2") (pin "17") (pinfunction "GPIO14_17") (pintype "bidirectional"))
    )
    (net (code "87") (name "unconnected-(U2-GPIO15-Pad18)") (class "Default")
      (node (ref "U2") (pin "18") (pinfunction "GPIO15_18") (pintype "bidirectional"))
    )
    (net (code "88") (name "unconnected-(U2-GPIO16-Pad27)") (class "Default")
      (node (ref "U2") (pin "27") (pinfunction "GPIO16_27") (pintype "bidirectional"))
    )
    (net (code "89") (name "unconnected-(U2-GPIO17-Pad28)") (class "Default")
      (node (ref "U2") (pin "28") (pinfunction "GPIO17_28") (pintype "bidirectional"))
    )
    (net (code "90") (name "unconnected-(U5-EN-Pad5)") (class "Default")
      (node (ref "U5") (pin "5") (pinfunction "EN_5") (pintype "bidirectional"))
    )
    (net (code "91") (name "unconnected-(U9-PA0-WKUP-Pad10)") (class "Default")
      (node (ref "U9") (pin "10") (pinfunction "PA0-WKUP_10") (pintype "bidirectional"))
    )
    (net (code "92") (name "unconnected-(U9-PA1-Pad11)") (class "Default")
      (node (ref "U9") (pin "11") (pinfunction "PA1_11") (pintype "bidirectional"))
    )
    (net (code "93") (name "unconnected-(U9-PA2-Pad12)") (class "Default")
      (node (ref "U9") (pin "12") (pinfunction "PA2_12") (pintype "bidirectional"))
    )
    (net (code "94") (name "unconnected-(U9-PA3-Pad13)") (class "Default")
      (node (ref "U9") (pin "13") (pinfunction "PA3_13") (pintype "bidirectional"))
    )
    (net (code "95") (name "unconnected-(U9-PA4-Pad14)") (class "Default")
      (node (ref "U9") (pin "14") (pinfunction "PA4_14") (pintype "bidirectional"))
    )
    (net (code "96") (name "unconnected-(U9-PA5-Pad15)") (class "Default")
      (node (ref "U9") (pin "15") (pinfunction "PA5_15") (pintype "bidirectional"))
    )
    (net (code "97") (name "unconnected-(U9-PA6-Pad16)") (class "Default")
      (node (ref "U9") (pin "16") (pinfunction "PA6_16") (pintype "bidirectional"))
    )
    (net (code "98") (name "unconnected-(U9-PA7-Pad17)") (class "Default")
      (node (ref "U9") (pin "17") (pinfunction "PA7_17") (pintype "bidirectional"))
    )
    (net (code "99") (name "unconnected-(U9-PA8-Pad29)") (class "Default")
      (node (ref "U9") (pin "29") (pinfunction "PA8_29") (pintype "bidirectional"))
    )
    (net (code "100") (name "unconnected-(U9-PA15-Pad38)") (class "Default")
      (node (ref "U9") (pin "38") (pinfunction "PA15_38") (pintype "bidirectional"))
    )
    (net (code "101") (name "unconnected-(U9-PB0-Pad18)") (class "Default")
      (node (ref "U9") (pin "18") (pinfunction "PB0_18") (pintype "bidirectional"))
    )
    (net (code "102") (name "unconnected-(U9-PB1-Pad19)") (class "Default")
      (node (ref "U9") (pin "19") (pinfunction "PB1_19") (pintype "bidirectional"))
    )
    (net (code "103") (name "unconnected-(U9-PB2-Pad20)") (class "Default")
      (node (ref "U9") (pin "20") (pinfunction "PB2_20") (pintype "bidirectional"))
    )
    (net (code "104") (name "unconnected-(U9-PB3-Pad39)") (class "Default")
      (node (ref "U9") (pin "39") (pinfunction "PB3_39") (pintype "bidirectional"))
    )
    (net (code "105") (name "unconnected-(U9-PB4-Pad40)") (class "Default")
      (node (ref "U9") (pin "40") (pinfunction "PB4_40") (pintype "bidirectional"))
    )
    (net (code "106") (name "unconnected-(U9-PB5-Pad41)") (class "Default")
      (node (ref "U9") (pin "41") (pinfunction "PB5_41") (pintype "bidirectional"))
    )
    (net (code "107") (name "unconnected-(U9-PB8-Pad45)") (class "Default")
      (node (ref "U9") (pin "45") (pinfunction "PB8_45") (pintype "bidirectional"))
    )
    (net (code "108") (name "unconnected-(U9-PB9-Pad46)") (class "Default")
      (node (ref "U9") (pin "46") (pinfunction "PB9_46") (pintype "bidirectional"))
    )
    (net (code "109") (name "unconnected-(U9-PB10-Pad21)") (class "Default")
      (node (ref "U9") (pin "21") (pinfunction "PB10_21") (pintype "bidirectional"))
    )
    (net (code "110") (name "unconnected-(U9-PB11-Pad22)") (class "Default")
      (node (ref "U9") (pin "22") (pinfunction "PB11_22") (pintype "bidirectional"))
    )
    (net (code "111") (name "unconnected-(U9-PB14-Pad27)") (class "Default")
      (node (ref "U9") (pin "27") (pinfunction "PB14_27") (pintype "bidirectional"))
    )
    (net (code "112") (name "unconnected-(U9-PB15-Pad28)") (class "Default")
      (node (ref "U9") (pin "28") (pinfunction "PB15_28") (pintype "bidirectional"))
    )
    (net (code "113") (name "unconnected-(U9-PC13-TAMPER-RTC-Pad2)") (class "Default")
      (node (ref "U9") (pin "2") (pinfunction "PC13-TAMPER-RTC_2") (pintype "bidirectional"))
    )
    (net (code "114") (name "unconnected-(U9-PC14-OSC32IN-Pad3)") (class "Default")
      (node (ref "U9") (pin "3") (pinfunction "PC14-OSC32IN_3") (pintype "bidirectional"))
    )
    (net (code "115") (name "unconnected-(U9-PC15-OSC32OUT-Pad4)") (class "Default")
      (node (ref "U9") (pin "4") (pinfunction "PC15-OSC32OUT_4") (pintype "bidirectional"))
    )
    (net (code "116") (name "unconnected-(U9-VBAT-Pad1)") (class "Default")
      (node (ref "U9") (pin "1") (pinfunction "VBAT_1") (pintype "bidirectional"))
    )
    (net (code "117") (name "unconnected-(X2-GND-Pad2)") (class "Default")
      (node (ref "X2") (pin "2") (pinfunction "GND_2") (pintype "bidirectional"))
    )
    (net (code "118") (name "unconnected-(X2-GND-Pad4)") (class "Default")
      (node (ref "X2") (pin "4") (pinfunction "GND_4") (pintype "bidirectional"))
    )
    (net (code "119") (name "unconnected-(X4-GND-Pad2)") (class "Default")
      (node (ref "X4") (pin "2") (pinfunction "GND_2") (pintype "bidirectional"))
    )
    (net (code "120") (name "unconnected-(X4-GND-Pad4)") (class "Default")
      (node (ref "X4") (pin "4") (pinfunction "GND_4") (pintype "bidirectional"))
    )
  )
)
